# FMC.net
KiCad netlist of a schematic drawn in Altium Designer
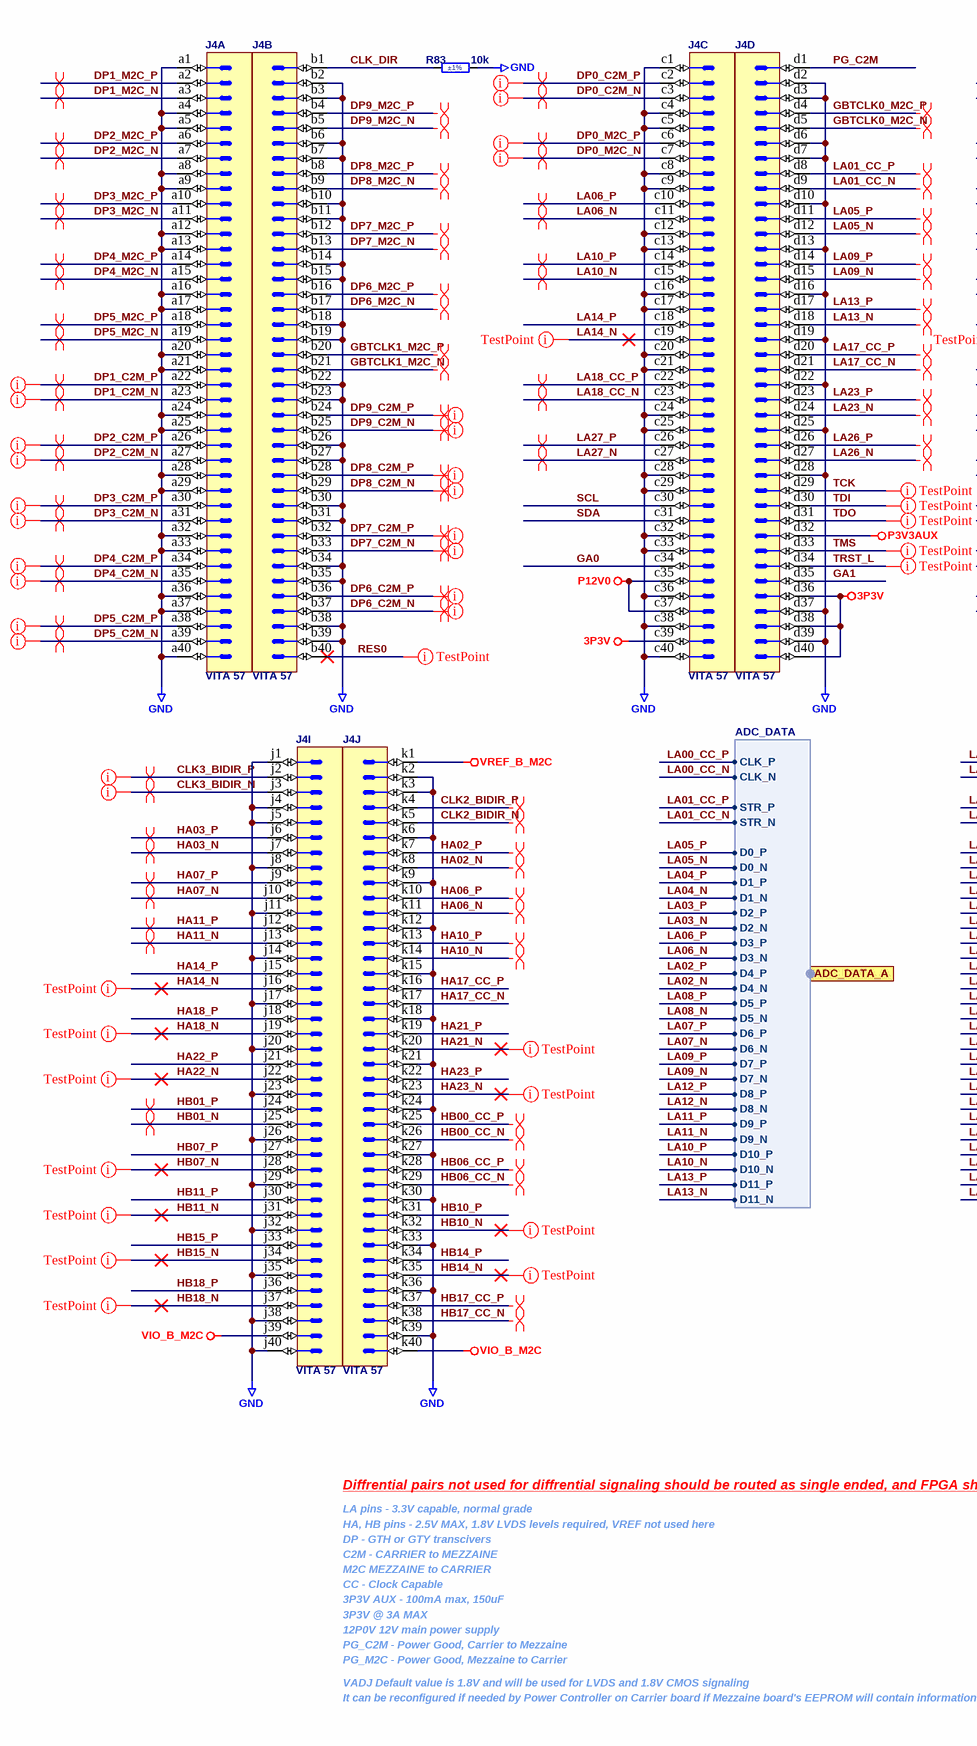
[diagram p0: FMC.SchDoc, left]
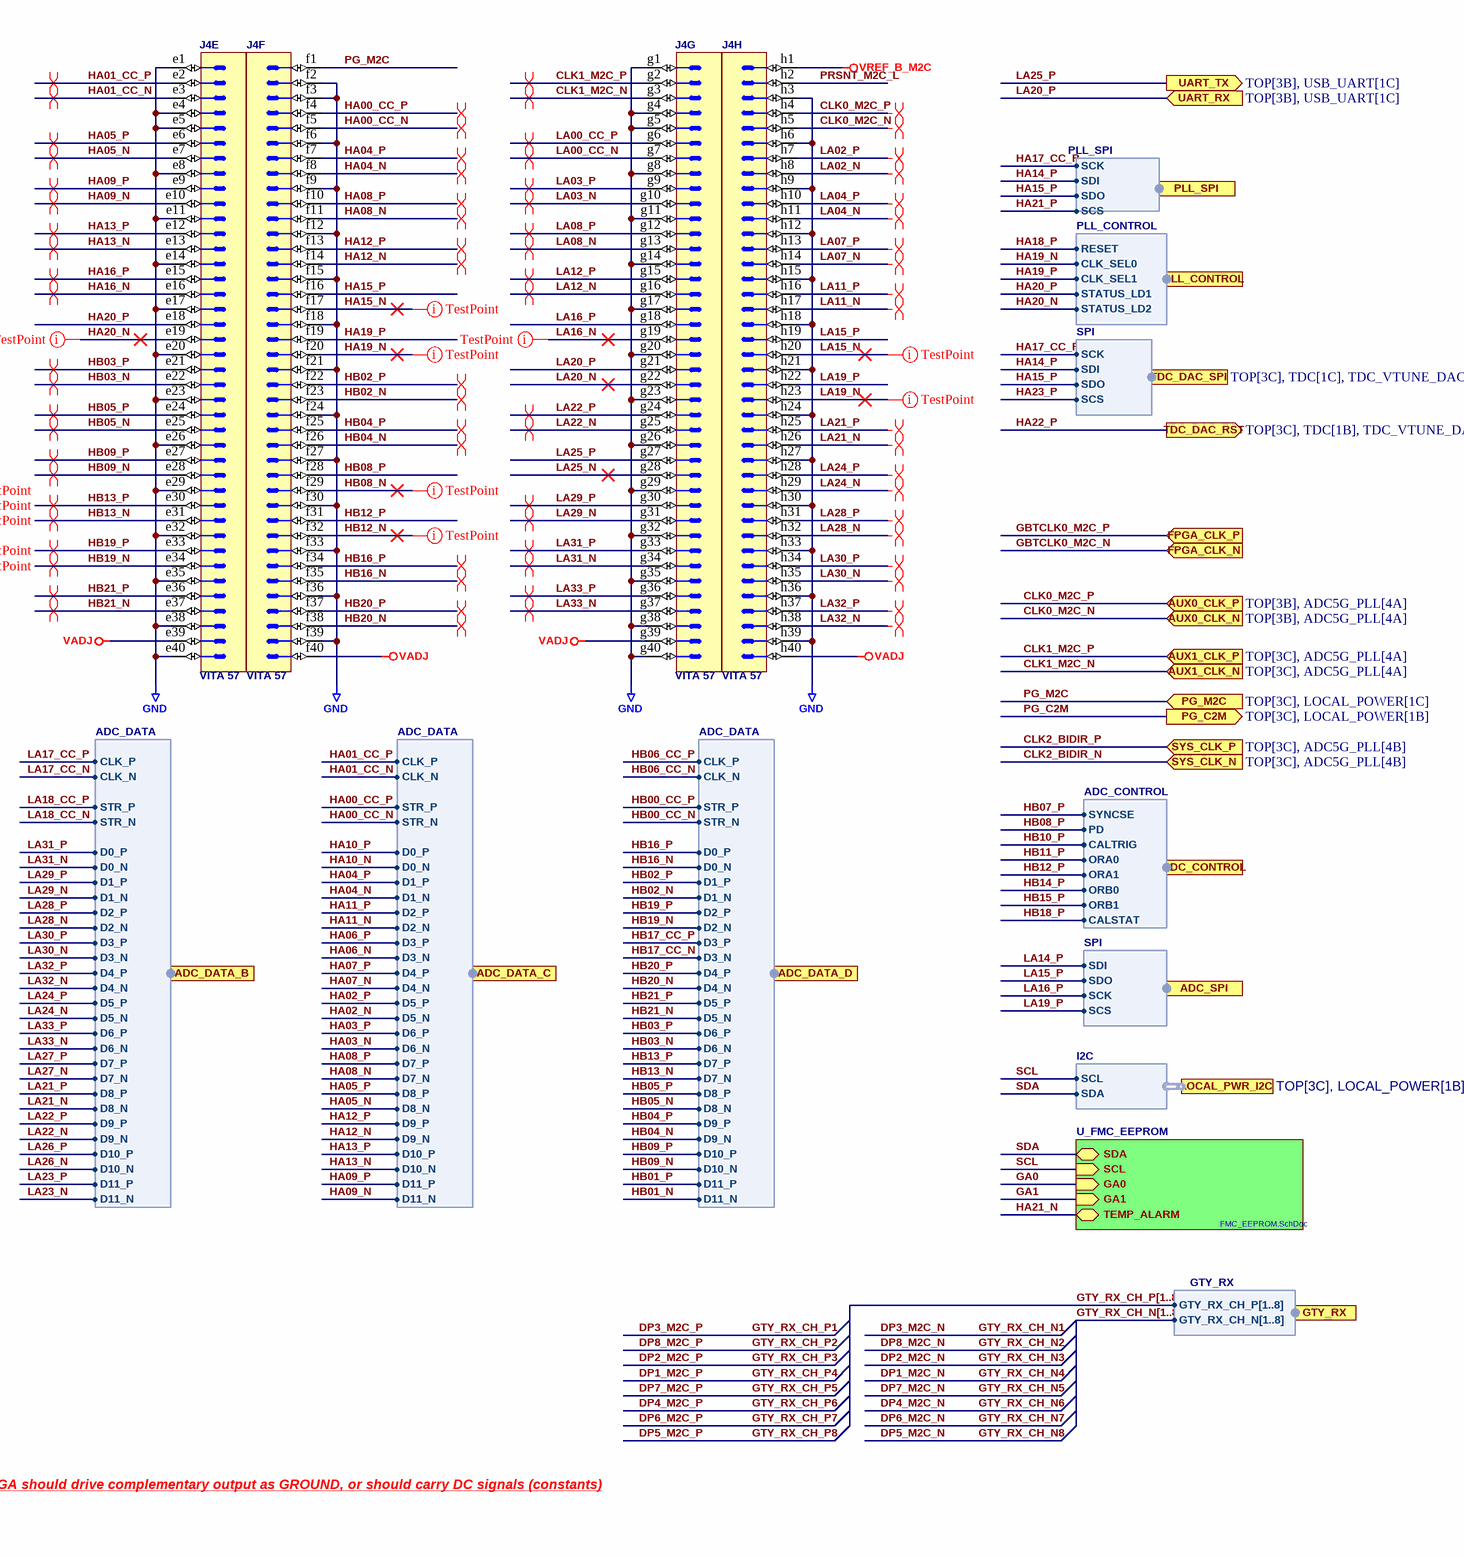
[diagram p1: FMC.SchDoc, right]

(export (version "E")
  (design (tool "Eeschema 10.0.6"))
  (components
    (comp (ref "J4")
      (value "VITA 57")
      (footprint "SAMTEC_ASP-134488-01")
      (description "Connector VITA 57, 400 Male contacts in 10 row abcdefghj")
      (fields
        (field (name "PART NUMBER") "SAMTEC_ASP-134488-01")
        (field (name "MANUFACTURER") "SAMTEC")
        (field (name "AUTHOR") "CERN DEM JLC")
      )
      (libsource (lib "Connectors") (part "Connector VITA 57 400 Male (abcdefghjk)"))
    )
    (comp (ref "R83")
      (value "10k")
      (footprint "RESC1005X40N")
      (description "Resistor - 1%")
      (fields
        (field (name "TOLERANCE") "±1%")
        (field (name "PART NUMBER") "R0402_10K_1%_0.0625W_100PPM")
        (field (name "POWER") "0.0625W")
        (field (name "AUTHOR") "CERN DEM JLC")
      )
      (libsource (lib "Resistors") (part "Resistor - 1%"))
    )
  )
  (nets
    (net (code "8") (name "/CLK0_M2C_N") (class "Default")
      (node (ref "J4") (pin "h5") (pinfunction "h5_h5") (pintype "bidirectional"))
    )
    (net (code "9") (name "/CLK0_M2C_P") (class "Default")
      (node (ref "J4") (pin "h4") (pinfunction "h4_h4") (pintype "bidirectional"))
    )
    (net (code "10") (name "/CLK1_M2C_N") (class "Default")
      (node (ref "J4") (pin "g3") (pinfunction "g3_g3") (pintype "bidirectional"))
    )
    (net (code "11") (name "/CLK1_M2C_P") (class "Default")
      (node (ref "J4") (pin "g2") (pinfunction "g2_g2") (pintype "bidirectional"))
    )
    (net (code "12") (name "/CLK2_BIDIR_N") (class "Default")
      (node (ref "J4") (pin "k5") (pinfunction "k5_k5") (pintype "bidirectional"))
    )
    (net (code "13") (name "/CLK2_BIDIR_P") (class "Default")
      (node (ref "J4") (pin "k4") (pinfunction "k4_k4") (pintype "bidirectional"))
    )
    (net (code "14") (name "/CLK3_BIDIR_N") (class "Default")
      (node (ref "J4") (pin "j3") (pinfunction "j3_j3") (pintype "bidirectional"))
    )
    (net (code "15") (name "/CLK3_BIDIR_P") (class "Default")
      (node (ref "J4") (pin "j2") (pinfunction "j2_j2") (pintype "bidirectional"))
    )
    (net (code "16") (name "/CLK_DIR") (class "Default")
      (node (ref "J4") (pin "b1") (pinfunction "b1_b1") (pintype "bidirectional"))
      (node (ref "R83") (pin "1") (pinfunction "1_1") (pintype "passive"))
    )
    (net (code "17") (name "/DP0_C2M_N") (class "Default")
      (node (ref "J4") (pin "c3") (pinfunction "c3_c3") (pintype "bidirectional"))
    )
    (net (code "18") (name "/DP0_C2M_P") (class "Default")
      (node (ref "J4") (pin "c2") (pinfunction "c2_c2") (pintype "bidirectional"))
    )
    (net (code "19") (name "/DP0_M2C_N") (class "Default")
      (node (ref "J4") (pin "c7") (pinfunction "c7_c7") (pintype "bidirectional"))
    )
    (net (code "20") (name "/DP0_M2C_P") (class "Default")
      (node (ref "J4") (pin "c6") (pinfunction "c6_c6") (pintype "bidirectional"))
    )
    (net (code "21") (name "/DP1_C2M_N") (class "Default")
      (node (ref "J4") (pin "a23") (pinfunction "a23_a23") (pintype "bidirectional"))
    )
    (net (code "22") (name "/DP1_C2M_P") (class "Default")
      (node (ref "J4") (pin "a22") (pinfunction "a22_a22") (pintype "bidirectional"))
    )
    (net (code "23") (name "/DP1_M2C_N") (class "Default")
      (node (ref "J4") (pin "a3") (pinfunction "a3_a3") (pintype "bidirectional"))
    )
    (net (code "24") (name "/DP2_C2M_N") (class "Default")
      (node (ref "J4") (pin "a27") (pinfunction "a27_a27") (pintype "bidirectional"))
    )
    (net (code "25") (name "/DP2_C2M_P") (class "Default")
      (node (ref "J4") (pin "a26") (pinfunction "a26_a26") (pintype "bidirectional"))
    )
    (net (code "26") (name "/DP2_M2C_N") (class "Default")
      (node (ref "J4") (pin "a7") (pinfunction "a7_a7") (pintype "bidirectional"))
    )
    (net (code "27") (name "/DP3_C2M_N") (class "Default")
      (node (ref "J4") (pin "a31") (pinfunction "a31_a31") (pintype "bidirectional"))
    )
    (net (code "28") (name "/DP3_C2M_P") (class "Default")
      (node (ref "J4") (pin "a30") (pinfunction "a30_a30") (pintype "bidirectional"))
    )
    (net (code "29") (name "/DP3_M2C_N") (class "Default")
      (node (ref "J4") (pin "a11") (pinfunction "a11_a11") (pintype "bidirectional"))
    )
    (net (code "30") (name "/DP4_C2M_N") (class "Default")
      (node (ref "J4") (pin "a35") (pinfunction "a35_a35") (pintype "bidirectional"))
    )
    (net (code "31") (name "/DP4_C2M_P") (class "Default")
      (node (ref "J4") (pin "a34") (pinfunction "a34_a34") (pintype "bidirectional"))
    )
    (net (code "32") (name "/DP4_M2C_N") (class "Default")
      (node (ref "J4") (pin "a15") (pinfunction "a15_a15") (pintype "bidirectional"))
    )
    (net (code "33") (name "/DP5_C2M_N") (class "Default")
      (node (ref "J4") (pin "a39") (pinfunction "a39_a39") (pintype "bidirectional"))
    )
    (net (code "34") (name "/DP5_C2M_P") (class "Default")
      (node (ref "J4") (pin "a38") (pinfunction "a38_a38") (pintype "bidirectional"))
    )
    (net (code "35") (name "/DP5_M2C_N") (class "Default")
      (node (ref "J4") (pin "a19") (pinfunction "a19_a19") (pintype "bidirectional"))
    )
    (net (code "36") (name "/DP6_C2M_N") (class "Default")
      (node (ref "J4") (pin "b37") (pinfunction "b37_b37") (pintype "bidirectional"))
    )
    (net (code "37") (name "/DP6_C2M_P") (class "Default")
      (node (ref "J4") (pin "b36") (pinfunction "b36_b36") (pintype "bidirectional"))
    )
    (net (code "38") (name "/DP6_M2C_N") (class "Default")
      (node (ref "J4") (pin "b17") (pinfunction "b17_b17") (pintype "bidirectional"))
    )
    (net (code "39") (name "/DP7_C2M_N") (class "Default")
      (node (ref "J4") (pin "b33") (pinfunction "b33_b33") (pintype "bidirectional"))
    )
    (net (code "40") (name "/DP7_C2M_P") (class "Default")
      (node (ref "J4") (pin "b32") (pinfunction "b32_b32") (pintype "bidirectional"))
    )
    (net (code "41") (name "/DP7_M2C_N") (class "Default")
      (node (ref "J4") (pin "b13") (pinfunction "b13_b13") (pintype "bidirectional"))
    )
    (net (code "42") (name "/DP8_C2M_N") (class "Default")
      (node (ref "J4") (pin "b29") (pinfunction "b29_b29") (pintype "bidirectional"))
    )
    (net (code "43") (name "/DP8_C2M_P") (class "Default")
      (node (ref "J4") (pin "b28") (pinfunction "b28_b28") (pintype "bidirectional"))
    )
    (net (code "44") (name "/DP8_M2C_N") (class "Default")
      (node (ref "J4") (pin "b9") (pinfunction "b9_b9") (pintype "bidirectional"))
    )
    (net (code "45") (name "/DP9_C2M_N") (class "Default")
      (node (ref "J4") (pin "b25") (pinfunction "b25_b25") (pintype "bidirectional"))
    )
    (net (code "46") (name "/DP9_C2M_P") (class "Default")
      (node (ref "J4") (pin "b24") (pinfunction "b24_b24") (pintype "bidirectional"))
    )
    (net (code "47") (name "/DP9_M2C_N") (class "Default")
      (node (ref "J4") (pin "b5") (pinfunction "b5_b5") (pintype "bidirectional"))
    )
    (net (code "48") (name "/DP9_M2C_P") (class "Default")
      (node (ref "J4") (pin "b4") (pinfunction "b4_b4") (pintype "bidirectional"))
    )
    (net (code "49") (name "/GA0") (class "Default")
      (node (ref "J4") (pin "c34") (pinfunction "c34_c34") (pintype "bidirectional"))
    )
    (net (code "50") (name "/GA1") (class "Default")
      (node (ref "J4") (pin "d35") (pinfunction "d35_d35") (pintype "bidirectional"))
    )
    (net (code "51") (name "/GBTCLK0_M2C_N") (class "Default")
      (node (ref "J4") (pin "d5") (pinfunction "d5_d5") (pintype "bidirectional"))
    )
    (net (code "52") (name "/GBTCLK0_M2C_P") (class "Default")
      (node (ref "J4") (pin "d4") (pinfunction "d4_d4") (pintype "bidirectional"))
    )
    (net (code "53") (name "/GBTCLK1_M2C_N") (class "Default")
      (node (ref "J4") (pin "b21") (pinfunction "b21_b21") (pintype "bidirectional"))
    )
    (net (code "54") (name "/GBTCLK1_M2C_P") (class "Default")
      (node (ref "J4") (pin "b20") (pinfunction "b20_b20") (pintype "bidirectional"))
    )
    (net (code "55") (name "/GTY_RX_CH_P1") (class "Default")
      (node (ref "J4") (pin "a10") (pinfunction "a10_a10") (pintype "bidirectional"))
    )
    (net (code "56") (name "/GTY_RX_CH_P2") (class "Default")
      (node (ref "J4") (pin "b8") (pinfunction "b8_b8") (pintype "bidirectional"))
    )
    (net (code "57") (name "/GTY_RX_CH_P3") (class "Default")
      (node (ref "J4") (pin "a6") (pinfunction "a6_a6") (pintype "bidirectional"))
    )
    (net (code "58") (name "/GTY_RX_CH_P4") (class "Default")
      (node (ref "J4") (pin "a2") (pinfunction "a2_a2") (pintype "bidirectional"))
    )
    (net (code "59") (name "/GTY_RX_CH_P5") (class "Default")
      (node (ref "J4") (pin "b12") (pinfunction "b12_b12") (pintype "bidirectional"))
    )
    (net (code "60") (name "/GTY_RX_CH_P6") (class "Default")
      (node (ref "J4") (pin "a14") (pinfunction "a14_a14") (pintype "bidirectional"))
    )
    (net (code "61") (name "/GTY_RX_CH_P7") (class "Default")
      (node (ref "J4") (pin "b16") (pinfunction "b16_b16") (pintype "bidirectional"))
    )
    (net (code "62") (name "/GTY_RX_CH_P8") (class "Default")
      (node (ref "J4") (pin "a18") (pinfunction "a18_a18") (pintype "bidirectional"))
    )
    (net (code "65") (name "/HA00_CC_N") (class "Default")
      (node (ref "J4") (pin "f5") (pinfunction "f5_f5") (pintype "bidirectional"))
    )
    (net (code "66") (name "/HA00_CC_P") (class "Default")
      (node (ref "J4") (pin "f4") (pinfunction "f4_f4") (pintype "bidirectional"))
    )
    (net (code "67") (name "/HA01_CC_N") (class "Default")
      (node (ref "J4") (pin "e3") (pinfunction "e3_e3") (pintype "bidirectional"))
    )
    (net (code "68") (name "/HA01_CC_P") (class "Default")
      (node (ref "J4") (pin "e2") (pinfunction "e2_e2") (pintype "bidirectional"))
    )
    (net (code "69") (name "/HA02_N") (class "Default")
      (node (ref "J4") (pin "k8") (pinfunction "k8_k8") (pintype "bidirectional"))
    )
    (net (code "70") (name "/HA02_P") (class "Default")
      (node (ref "J4") (pin "k7") (pinfunction "k7_k7") (pintype "bidirectional"))
    )
    (net (code "71") (name "/HA03_N") (class "Default")
      (node (ref "J4") (pin "j7") (pinfunction "j7_j7") (pintype "bidirectional"))
    )
    (net (code "72") (name "/HA03_P") (class "Default")
      (node (ref "J4") (pin "j6") (pinfunction "j6_j6") (pintype "bidirectional"))
    )
    (net (code "73") (name "/HA04_N") (class "Default")
      (node (ref "J4") (pin "f8") (pinfunction "f8_f8") (pintype "bidirectional"))
    )
    (net (code "74") (name "/HA04_P") (class "Default")
      (node (ref "J4") (pin "f7") (pinfunction "f7_f7") (pintype "bidirectional"))
    )
    (net (code "75") (name "/HA05_N") (class "Default")
      (node (ref "J4") (pin "e7") (pinfunction "e7_e7") (pintype "bidirectional"))
    )
    (net (code "76") (name "/HA05_P") (class "Default")
      (node (ref "J4") (pin "e6") (pinfunction "e6_e6") (pintype "bidirectional"))
    )
    (net (code "77") (name "/HA06_N") (class "Default")
      (node (ref "J4") (pin "k11") (pinfunction "k11_k11") (pintype "bidirectional"))
    )
    (net (code "78") (name "/HA06_P") (class "Default")
      (node (ref "J4") (pin "k10") (pinfunction "k10_k10") (pintype "bidirectional"))
    )
    (net (code "79") (name "/HA07_N") (class "Default")
      (node (ref "J4") (pin "j10") (pinfunction "j10_j10") (pintype "bidirectional"))
    )
    (net (code "80") (name "/HA07_P") (class "Default")
      (node (ref "J4") (pin "j9") (pinfunction "j9_j9") (pintype "bidirectional"))
    )
    (net (code "81") (name "/HA08_N") (class "Default")
      (node (ref "J4") (pin "f11") (pinfunction "f11_f11") (pintype "bidirectional"))
    )
    (net (code "82") (name "/HA08_P") (class "Default")
      (node (ref "J4") (pin "f10") (pinfunction "f10_f10") (pintype "bidirectional"))
    )
    (net (code "83") (name "/HA09_N") (class "Default")
      (node (ref "J4") (pin "e10") (pinfunction "e10_e10") (pintype "bidirectional"))
    )
    (net (code "84") (name "/HA09_P") (class "Default")
      (node (ref "J4") (pin "e9") (pinfunction "e9_e9") (pintype "bidirectional"))
    )
    (net (code "85") (name "/HA10_N") (class "Default")
      (node (ref "J4") (pin "k14") (pinfunction "k14_k14") (pintype "bidirectional"))
    )
    (net (code "86") (name "/HA10_P") (class "Default")
      (node (ref "J4") (pin "k13") (pinfunction "k13_k13") (pintype "bidirectional"))
    )
    (net (code "87") (name "/HA11_N") (class "Default")
      (node (ref "J4") (pin "j13") (pinfunction "j13_j13") (pintype "bidirectional"))
    )
    (net (code "88") (name "/HA11_P") (class "Default")
      (node (ref "J4") (pin "j12") (pinfunction "j12_j12") (pintype "bidirectional"))
    )
    (net (code "89") (name "/HA12_N") (class "Default")
      (node (ref "J4") (pin "f14") (pinfunction "f14_f14") (pintype "bidirectional"))
    )
    (net (code "90") (name "/HA12_P") (class "Default")
      (node (ref "J4") (pin "f13") (pinfunction "f13_f13") (pintype "bidirectional"))
    )
    (net (code "91") (name "/HA13_N") (class "Default")
      (node (ref "J4") (pin "e13") (pinfunction "e13_e13") (pintype "bidirectional"))
    )
    (net (code "92") (name "/HA13_P") (class "Default")
      (node (ref "J4") (pin "e12") (pinfunction "e12_e12") (pintype "bidirectional"))
    )
    (net (code "93") (name "/HA14_N") (class "Default")
      (node (ref "J4") (pin "j16") (pinfunction "j16_j16") (pintype "bidirectional"))
    )
    (net (code "94") (name "/HA14_P") (class "Default")
      (node (ref "J4") (pin "j15") (pinfunction "j15_j15") (pintype "bidirectional"))
    )
    (net (code "95") (name "/HA15_N") (class "Default")
      (node (ref "J4") (pin "f17") (pinfunction "f17_f17") (pintype "bidirectional"))
    )
    (net (code "96") (name "/HA15_P") (class "Default")
      (node (ref "J4") (pin "f16") (pinfunction "f16_f16") (pintype "bidirectional"))
    )
    (net (code "97") (name "/HA16_N") (class "Default")
      (node (ref "J4") (pin "e16") (pinfunction "e16_e16") (pintype "bidirectional"))
    )
    (net (code "98") (name "/HA16_P") (class "Default")
      (node (ref "J4") (pin "e15") (pinfunction "e15_e15") (pintype "bidirectional"))
    )
    (net (code "99") (name "/HA17_CC_N") (class "Default")
      (node (ref "J4") (pin "k17") (pinfunction "k17_k17") (pintype "bidirectional"))
    )
    (net (code "100") (name "/HA17_CC_P") (class "Default")
      (node (ref "J4") (pin "k16") (pinfunction "k16_k16") (pintype "bidirectional"))
    )
    (net (code "101") (name "/HA18_N") (class "Default")
      (node (ref "J4") (pin "j19") (pinfunction "j19_j19") (pintype "bidirectional"))
    )
    (net (code "102") (name "/HA18_P") (class "Default")
      (node (ref "J4") (pin "j18") (pinfunction "j18_j18") (pintype "bidirectional"))
    )
    (net (code "103") (name "/HA19_N") (class "Default")
      (node (ref "J4") (pin "f20") (pinfunction "f20_f20") (pintype "bidirectional"))
    )
    (net (code "104") (name "/HA19_P") (class "Default")
      (node (ref "J4") (pin "f19") (pinfunction "f19_f19") (pintype "bidirectional"))
    )
    (net (code "105") (name "/HA20_N") (class "Default")
      (node (ref "J4") (pin "e19") (pinfunction "e19_e19") (pintype "bidirectional"))
    )
    (net (code "106") (name "/HA20_P") (class "Default")
      (node (ref "J4") (pin "e18") (pinfunction "e18_e18") (pintype "bidirectional"))
    )
    (net (code "107") (name "/HA21_N") (class "Default")
      (node (ref "J4") (pin "k20") (pinfunction "k20_k20") (pintype "bidirectional"))
    )
    (net (code "108") (name "/HA21_P") (class "Default")
      (node (ref "J4") (pin "k19") (pinfunction "k19_k19") (pintype "bidirectional"))
    )
    (net (code "109") (name "/HA22_N") (class "Default")
      (node (ref "J4") (pin "j22") (pinfunction "j22_j22") (pintype "bidirectional"))
    )
    (net (code "110") (name "/HA22_P") (class "Default")
      (node (ref "J4") (pin "j21") (pinfunction "j21_j21") (pintype "bidirectional"))
    )
    (net (code "111") (name "/HA23_N") (class "Default")
      (node (ref "J4") (pin "k23") (pinfunction "k23_k23") (pintype "bidirectional"))
    )
    (net (code "112") (name "/HA23_P") (class "Default")
      (node (ref "J4") (pin "k22") (pinfunction "k22_k22") (pintype "bidirectional"))
    )
    (net (code "113") (name "/HB00_CC_N") (class "Default")
      (node (ref "J4") (pin "k26") (pinfunction "k26_k26") (pintype "bidirectional"))
    )
    (net (code "114") (name "/HB00_CC_P") (class "Default")
      (node (ref "J4") (pin "k25") (pinfunction "k25_k25") (pintype "bidirectional"))
    )
    (net (code "115") (name "/HB01_N") (class "Default")
      (node (ref "J4") (pin "j25") (pinfunction "j25_j25") (pintype "bidirectional"))
    )
    (net (code "116") (name "/HB01_P") (class "Default")
      (node (ref "J4") (pin "j24") (pinfunction "j24_j24") (pintype "bidirectional"))
    )
    (net (code "117") (name "/HB02_N") (class "Default")
      (node (ref "J4") (pin "f23") (pinfunction "f23_f23") (pintype "bidirectional"))
    )
    (net (code "118") (name "/HB02_P") (class "Default")
      (node (ref "J4") (pin "f22") (pinfunction "f22_f22") (pintype "bidirectional"))
    )
    (net (code "119") (name "/HB03_N") (class "Default")
      (node (ref "J4") (pin "e22") (pinfunction "e22_e22") (pintype "bidirectional"))
    )
    (net (code "120") (name "/HB03_P") (class "Default")
      (node (ref "J4") (pin "e21") (pinfunction "e21_e21") (pintype "bidirectional"))
    )
    (net (code "121") (name "/HB04_N") (class "Default")
      (node (ref "J4") (pin "f26") (pinfunction "f26_f26") (pintype "bidirectional"))
    )
    (net (code "122") (name "/HB04_P") (class "Default")
      (node (ref "J4") (pin "f25") (pinfunction "f25_f25") (pintype "bidirectional"))
    )
    (net (code "123") (name "/HB05_N") (class "Default")
      (node (ref "J4") (pin "e25") (pinfunction "e25_e25") (pintype "bidirectional"))
    )
    (net (code "124") (name "/HB05_P") (class "Default")
      (node (ref "J4") (pin "e24") (pinfunction "e24_e24") (pintype "bidirectional"))
    )
    (net (code "125") (name "/HB06_CC_N") (class "Default")
      (node (ref "J4") (pin "k29") (pinfunction "k29_k29") (pintype "bidirectional"))
    )
    (net (code "126") (name "/HB06_CC_P") (class "Default")
      (node (ref "J4") (pin "k28") (pinfunction "k28_k28") (pintype "bidirectional"))
    )
    (net (code "127") (name "/HB07_N") (class "Default")
      (node (ref "J4") (pin "j28") (pinfunction "j28_j28") (pintype "bidirectional"))
    )
    (net (code "128") (name "/HB07_P") (class "Default")
      (node (ref "J4") (pin "j27") (pinfunction "j27_j27") (pintype "bidirectional"))
    )
    (net (code "129") (name "/HB08_N") (class "Default")
      (node (ref "J4") (pin "f29") (pinfunction "f29_f29") (pintype "bidirectional"))
    )
    (net (code "130") (name "/HB08_P") (class "Default")
      (node (ref "J4") (pin "f28") (pinfunction "f28_f28") (pintype "bidirectional"))
    )
    (net (code "131") (name "/HB09_N") (class "Default")
      (node (ref "J4") (pin "e28") (pinfunction "e28_e28") (pintype "bidirectional"))
    )
    (net (code "132") (name "/HB09_P") (class "Default")
      (node (ref "J4") (pin "e27") (pinfunction "e27_e27") (pintype "bidirectional"))
    )
    (net (code "133") (name "/HB10_N") (class "Default")
      (node (ref "J4") (pin "k32") (pinfunction "k32_k32") (pintype "bidirectional"))
    )
    (net (code "134") (name "/HB10_P") (class "Default")
      (node (ref "J4") (pin "k31") (pinfunction "k31_k31") (pintype "bidirectional"))
    )
    (net (code "135") (name "/HB11_N") (class "Default")
      (node (ref "J4") (pin "j31") (pinfunction "j31_j31") (pintype "bidirectional"))
    )
    (net (code "136") (name "/HB11_P") (class "Default")
      (node (ref "J4") (pin "j30") (pinfunction "j30_j30") (pintype "bidirectional"))
    )
    (net (code "137") (name "/HB12_N") (class "Default")
      (node (ref "J4") (pin "f32") (pinfunction "f32_f32") (pintype "bidirectional"))
    )
    (net (code "138") (name "/HB12_P") (class "Default")
      (node (ref "J4") (pin "f31") (pinfunction "f31_f31") (pintype "bidirectional"))
    )
    (net (code "139") (name "/HB13_N") (class "Default")
      (node (ref "J4") (pin "e31") (pinfunction "e31_e31") (pintype "bidirectional"))
    )
    (net (code "140") (name "/HB13_P") (class "Default")
      (node (ref "J4") (pin "e30") (pinfunction "e30_e30") (pintype "bidirectional"))
    )
    (net (code "141") (name "/HB14_N") (class "Default")
      (node (ref "J4") (pin "k35") (pinfunction "k35_k35") (pintype "bidirectional"))
    )
    (net (code "142") (name "/HB14_P") (class "Default")
      (node (ref "J4") (pin "k34") (pinfunction "k34_k34") (pintype "bidirectional"))
    )
    (net (code "143") (name "/HB15_N") (class "Default")
      (node (ref "J4") (pin "j34") (pinfunction "j34_j34") (pintype "bidirectional"))
    )
    (net (code "144") (name "/HB15_P") (class "Default")
      (node (ref "J4") (pin "j33") (pinfunction "j33_j33") (pintype "bidirectional"))
    )
    (net (code "145") (name "/HB16_N") (class "Default")
      (node (ref "J4") (pin "f35") (pinfunction "f35_f35") (pintype "bidirectional"))
    )
    (net (code "146") (name "/HB16_P") (class "Default")
      (node (ref "J4") (pin "f34") (pinfunction "f34_f34") (pintype "bidirectional"))
    )
    (net (code "147") (name "/HB17_CC_N") (class "Default")
      (node (ref "J4") (pin "k38") (pinfunction "k38_k38") (pintype "bidirectional"))
    )
    (net (code "148") (name "/HB17_CC_P") (class "Default")
      (node (ref "J4") (pin "k37") (pinfunction "k37_k37") (pintype "bidirectional"))
    )
    (net (code "149") (name "/HB18_N") (class "Default")
      (node (ref "J4") (pin "j37") (pinfunction "j37_j37") (pintype "bidirectional"))
    )
    (net (code "150") (name "/HB18_P") (class "Default")
      (node (ref "J4") (pin "j36") (pinfunction "j36_j36") (pintype "bidirectional"))
    )
    (net (code "151") (name "/HB19_N") (class "Default")
      (node (ref "J4") (pin "e34") (pinfunction "e34_e34") (pintype "bidirectional"))
    )
    (net (code "152") (name "/HB19_P") (class "Default")
      (node (ref "J4") (pin "e33") (pinfunction "e33_e33") (pintype "bidirectional"))
    )
    (net (code "153") (name "/HB20_N") (class "Default")
      (node (ref "J4") (pin "f38") (pinfunction "f38_f38") (pintype "bidirectional"))
    )
    (net (code "154") (name "/HB20_P") (class "Default")
      (node (ref "J4") (pin "f37") (pinfunction "f37_f37") (pintype "bidirectional"))
    )
    (net (code "155") (name "/HB21_N") (class "Default")
      (node (ref "J4") (pin "e37") (pinfunction "e37_e37") (pintype "bidirectional"))
    )
    (net (code "156") (name "/HB21_P") (class "Default")
      (node (ref "J4") (pin "e36") (pinfunction "e36_e36") (pintype "bidirectional"))
    )
    (net (code "157") (name "/LA00_CC_N") (class "Default")
      (node (ref "J4") (pin "g7") (pinfunction "g7_g7") (pintype "bidirectional"))
    )
    (net (code "158") (name "/LA00_CC_P") (class "Default")
      (node (ref "J4") (pin "g6") (pinfunction "g6_g6") (pintype "bidirectional"))
    )
    (net (code "159") (name "/LA01_CC_N") (class "Default")
      (node (ref "J4") (pin "d9") (pinfunction "d9_d9") (pintype "bidirectional"))
    )
    (net (code "160") (name "/LA01_CC_P") (class "Default")
      (node (ref "J4") (pin "d8") (pinfunction "d8_d8") (pintype "bidirectional"))
    )
    (net (code "161") (name "/LA02_N") (class "Default")
      (node (ref "J4") (pin "h8") (pinfunction "h8_h8") (pintype "bidirectional"))
    )
    (net (code "162") (name "/LA02_P") (class "Default")
      (node (ref "J4") (pin "h7") (pinfunction "h7_h7") (pintype "bidirectional"))
    )
    (net (code "163") (name "/LA03_N") (class "Default")
      (node (ref "J4") (pin "g10") (pinfunction "g10_g10") (pintype "bidirectional"))
    )
    (net (code "164") (name "/LA03_P") (class "Default")
      (node (ref "J4") (pin "g9") (pinfunction "g9_g9") (pintype "bidirectional"))
    )
    (net (code "165") (name "/LA04_N") (class "Default")
      (node (ref "J4") (pin "h11") (pinfunction "h11_h11") (pintype "bidirectional"))
    )
    (net (code "166") (name "/LA04_P") (class "Default")
      (node (ref "J4") (pin "h10") (pinfunction "h10_h10") (pintype "bidirectional"))
    )
    (net (code "167") (name "/LA05_N") (class "Default")
      (node (ref "J4") (pin "d12") (pinfunction "d12_d12") (pintype "bidirectional"))
    )
    (net (code "168") (name "/LA05_P") (class "Default")
      (node (ref "J4") (pin "d11") (pinfunction "d11_d11") (pintype "bidirectional"))
    )
    (net (code "169") (name "/LA06_N") (class "Default")
      (node (ref "J4") (pin "c11") (pinfunction "c11_c11") (pintype "bidirectional"))
    )
    (net (code "170") (name "/LA06_P") (class "Default")
      (node (ref "J4") (pin "c10") (pinfunction "c10_c10") (pintype "bidirectional"))
    )
    (net (code "171") (name "/LA07_N") (class "Default")
      (node (ref "J4") (pin "h14") (pinfunction "h14_h14") (pintype "bidirectional"))
    )
    (net (code "172") (name "/LA07_P") (class "Default")
      (node (ref "J4") (pin "h13") (pinfunction "h13_h13") (pintype "bidirectional"))
    )
    (net (code "173") (name "/LA08_N") (class "Default")
      (node (ref "J4") (pin "g13") (pinfunction "g13_g13") (pintype "bidirectional"))
    )
    (net (code "174") (name "/LA08_P") (class "Default")
      (node (ref "J4") (pin "g12") (pinfunction "g12_g12") (pintype "bidirectional"))
    )
    (net (code "175") (name "/LA09_N") (class "Default")
      (node (ref "J4") (pin "d15") (pinfunction "d15_d15") (pintype "bidirectional"))
    )
    (net (code "176") (name "/LA09_P") (class "Default")
      (node (ref "J4") (pin "d14") (pinfunction "d14_d14") (pintype "bidirectional"))
    )
    (net (code "177") (name "/LA10_N") (class "Default")
      (node (ref "J4") (pin "c15") (pinfunction "c15_c15") (pintype "bidirectional"))
    )
    (net (code "178") (name "/LA10_P") (class "Default")
      (node (ref "J4") (pin "c14") (pinfunction "c14_c14") (pintype "bidirectional"))
    )
    (net (code "179") (name "/LA11_N") (class "Default")
      (node (ref "J4") (pin "h17") (pinfunction "h17_h17") (pintype "bidirectional"))
    )
    (net (code "180") (name "/LA11_P") (class "Default")
      (node (ref "J4") (pin "h16") (pinfunction "h16_h16") (pintype "bidirectional"))
    )
    (net (code "181") (name "/LA12_N") (class "Default")
      (node (ref "J4") (pin "g16") (pinfunction "g16_g16") (pintype "bidirectional"))
    )
    (net (code "182") (name "/LA12_P") (class "Default")
      (node (ref "J4") (pin "g15") (pinfunction "g15_g15") (pintype "bidirectional"))
    )
    (net (code "183") (name "/LA13_N") (class "Default")
      (node (ref "J4") (pin "d18") (pinfunction "d18_d18") (pintype "bidirectional"))
    )
    (net (code "184") (name "/LA13_P") (class "Default")
      (node (ref "J4") (pin "d17") (pinfunction "d17_d17") (pintype "bidirectional"))
    )
    (net (code "185") (name "/LA14_N") (class "Default")
      (node (ref "J4") (pin "c19") (pinfunction "c19_c19") (pintype "bidirectional"))
    )
    (net (code "186") (name "/LA14_P") (class "Default")
      (node (ref "J4") (pin "c18") (pinfunction "c18_c18") (pintype "bidirectional"))
    )
    (net (code "187") (name "/LA15_N") (class "Default")
      (node (ref "J4") (pin "h20") (pinfunction "h20_h20") (pintype "bidirectional"))
    )
    (net (code "188") (name "/LA15_P") (class "Default")
      (node (ref "J4") (pin "h19") (pinfunction "h19_h19") (pintype "bidirectional"))
    )
    (net (code "189") (name "/LA16_N") (class "Default")
      (node (ref "J4") (pin "g19") (pinfunction "g19_g19") (pintype "bidirectional"))
    )
    (net (code "190") (name "/LA16_P") (class "Default")
      (node (ref "J4") (pin "g18") (pinfunction "g18_g18") (pintype "bidirectional"))
    )
    (net (code "191") (name "/LA17_CC_N") (class "Default")
      (node (ref "J4") (pin "d21") (pinfunction "d21_d21") (pintype "bidirectional"))
    )
    (net (code "192") (name "/LA17_CC_P") (class "Default")
      (node (ref "J4") (pin "d20") (pinfunction "d20_d20") (pintype "bidirectional"))
    )
    (net (code "193") (name "/LA18_CC_N") (class "Default")
      (node (ref "J4") (pin "c23") (pinfunction "c23_c23") (pintype "bidirectional"))
    )
    (net (code "194") (name "/LA18_CC_P") (class "Default")
      (node (ref "J4") (pin "c22") (pinfunction "c22_c22") (pintype "bidirectional"))
    )
    (net (code "195") (name "/LA19_N") (class "Default")
      (node (ref "J4") (pin "h23") (pinfunction "h23_h23") (pintype "bidirectional"))
    )
    (net (code "196") (name "/LA19_P") (class "Default")
      (node (ref "J4") (pin "h22") (pinfunction "h22_h22") (pintype "bidirectional"))
    )
    (net (code "197") (name "/LA20_N") (class "Default")
      (node (ref "J4") (pin "g22") (pinfunction "g22_g22") (pintype "bidirectional"))
    )
    (net (code "198") (name "/LA20_P") (class "Default")
      (node (ref "J4") (pin "g21") (pinfunction "g21_g21") (pintype "bidirectional"))
    )
    (net (code "199") (name "/LA21_N") (class "Default")
      (node (ref "J4") (pin "h26") (pinfunction "h26_h26") (pintype "bidirectional"))
    )
    (net (code "200") (name "/LA21_P") (class "Default")
      (node (ref "J4") (pin "h25") (pinfunction "h25_h25") (pintype "bidirectional"))
    )
    (net (code "201") (name "/LA22_N") (class "Default")
      (node (ref "J4") (pin "g25") (pinfunction "g25_g25") (pintype "bidirectional"))
    )
    (net (code "202") (name "/LA22_P") (class "Default")
      (node (ref "J4") (pin "g24") (pinfunction "g24_g24") (pintype "bidirectional"))
    )
    (net (code "203") (name "/LA23_N") (class "Default")
      (node (ref "J4") (pin "d24") (pinfunction "d24_d24") (pintype "bidirectional"))
    )
    (net (code "204") (name "/LA23_P") (class "Default")
      (node (ref "J4") (pin "d23") (pinfunction "d23_d23") (pintype "bidirectional"))
    )
    (net (code "205") (name "/LA24_N") (class "Default")
      (node (ref "J4") (pin "h29") (pinfunction "h29_h29") (pintype "bidirectional"))
    )
    (net (code "206") (name "/LA24_P") (class "Default")
      (node (ref "J4") (pin "h28") (pinfunction "h28_h28") (pintype "bidirectional"))
    )
    (net (code "207") (name "/LA25_N") (class "Default")
      (node (ref "J4") (pin "g28") (pinfunction "g28_g28") (pintype "bidirectional"))
    )
    (net (code "208") (name "/LA25_P") (class "Default")
      (node (ref "J4") (pin "g27") (pinfunction "g27_g27") (pintype "bidirectional"))
    )
    (net (code "209") (name "/LA26_N") (class "Default")
      (node (ref "J4") (pin "d27") (pinfunction "d27_d27") (pintype "bidirectional"))
    )
    (net (code "210") (name "/LA26_P") (class "Default")
      (node (ref "J4") (pin "d26") (pinfunction "d26_d26") (pintype "bidirectional"))
    )
    (net (code "211") (name "/LA27_N") (class "Default")
      (node (ref "J4") (pin "c27") (pinfunction "c27_c27") (pintype "bidirectional"))
    )
    (net (code "212") (name "/LA27_P") (class "Default")
      (node (ref "J4") (pin "c26") (pinfunction "c26_c26") (pintype "bidirectional"))
    )
    (net (code "213") (name "/LA28_N") (class "Default")
      (node (ref "J4") (pin "h32") (pinfunction "h32_h32") (pintype "bidirectional"))
    )
    (net (code "214") (name "/LA28_P") (class "Default")
      (node (ref "J4") (pin "h31") (pinfunction "h31_h31") (pintype "bidirectional"))
    )
    (net (code "215") (name "/LA29_N") (class "Default")
      (node (ref "J4") (pin "g31") (pinfunction "g31_g31") (pintype "bidirectional"))
    )
    (net (code "216") (name "/LA29_P") (class "Default")
      (node (ref "J4") (pin "g30") (pinfunction "g30_g30") (pintype "bidirectional"))
    )
    (net (code "217") (name "/LA30_N") (class "Default")
      (node (ref "J4") (pin "h35") (pinfunction "h35_h35") (pintype "bidirectional"))
    )
    (net (code "218") (name "/LA30_P") (class "Default")
      (node (ref "J4") (pin "h34") (pinfunction "h34_h34") (pintype "bidirectional"))
    )
    (net (code "219") (name "/LA31_N") (class "Default")
      (node (ref "J4") (pin "g34") (pinfunction "g34_g34") (pintype "bidirectional"))
    )
    (net (code "220") (name "/LA31_P") (class "Default")
      (node (ref "J4") (pin "g33") (pinfunction "g33_g33") (pintype "bidirectional"))
    )
    (net (code "221") (name "/LA32_N") (class "Default")
      (node (ref "J4") (pin "h38") (pinfunction "h38_h38") (pintype "bidirectional"))
    )
    (net (code "222") (name "/LA32_P") (class "Default")
      (node (ref "J4") (pin "h37") (pinfunction "h37_h37") (pintype "bidirectional"))
    )
    (net (code "223") (name "/LA33_N") (class "Default")
      (node (ref "J4") (pin "g37") (pinfunction "g37_g37") (pintype "bidirectional"))
    )
    (net (code "224") (name "/LA33_P") (class "Default")
      (node (ref "J4") (pin "g36") (pinfunction "g36_g36") (pintype "bidirectional"))
    )
    (net (code "225") (name "/PG_C2M") (class "Default")
      (node (ref "J4") (pin "d1") (pinfunction "d1_d1") (pintype "bidirectional"))
    )
    (net (code "226") (name "/PG_M2C") (class "Default")
      (node (ref "J4") (pin "f1") (pinfunction "f1_f1") (pintype "bidirectional"))
    )
    (net (code "227") (name "/PRSNT_M2C_L") (class "Default")
      (node (ref "J4") (pin "h2") (pinfunction "h2_h2") (pintype "bidirectional"))
    )
    (net (code "228") (name "/RES0") (class "Default")
      (node (ref "J4") (pin "b40") (pinfunction "b40_b40") (pintype "bidirectional+no_connect"))
    )
    (net (code "229") (name "/SCL") (class "Default")
      (node (ref "J4") (pin "c30") (pinfunction "c30_c30") (pintype "bidirectional"))
    )
    (net (code "230") (name "/SDA") (class "Default")
      (node (ref "J4") (pin "c31") (pinfunction "c31_c31") (pintype "bidirectional"))
    )
    (net (code "231") (name "/TCK") (class "Default")
      (node (ref "J4") (pin "d29") (pinfunction "d29_d29") (pintype "bidirectional"))
    )
    (net (code "232") (name "/TDI") (class "Default")
      (node (ref "J4") (pin "d30") (pinfunction "d30_d30") (pintype "bidirectional"))
    )
    (net (code "233") (name "/TDO") (class "Default")
      (node (ref "J4") (pin "d31") (pinfunction "d31_d31") (pintype "bidirectional"))
    )
    (net (code "234") (name "/TMS") (class "Default")
      (node (ref "J4") (pin "d33") (pinfunction "d33_d33") (pintype "bidirectional"))
    )
    (net (code "235") (name "/TRST_L") (class "Default")
      (node (ref "J4") (pin "d34") (pinfunction "d34_d34") (pintype "bidirectional"))
    )
    (net (code "242") (name "3P3V") (class "Default")
      (node (ref "J4") (pin "c39") (pinfunction "c39_c39") (pintype "bidirectional"))
      (node (ref "J4") (pin "d36") (pinfunction "d36_d36") (pintype "bidirectional"))
      (node (ref "J4") (pin "d38") (pinfunction "d38_d38") (pintype "bidirectional"))
      (node (ref "J4") (pin "d40") (pinfunction "d40_d40") (pintype "bidirectional"))
    )
    (net (code "243") (name "GND") (class "Default")
      (node (ref "J4") (pin "a1") (pinfunction "a1_a1") (pintype "bidirectional"))
      (node (ref "J4") (pin "a12") (pinfunction "a12_a12") (pintype "bidirectional"))
      (node (ref "J4") (pin "a13") (pinfunction "a13_a13") (pintype "bidirectional"))
      (node (ref "J4") (pin "a16") (pinfunction "a16_a16") (pintype "bidirectional"))
      (node (ref "J4") (pin "a17") (pinfunction "a17_a17") (pintype "bidirectional"))
      (node (ref "J4") (pin "a20") (pinfunction "a20_a20") (pintype "bidirectional"))
      (node (ref "J4") (pin "a21") (pinfunction "a21_a21") (pintype "bidirectional"))
      (node (ref "J4") (pin "a24") (pinfunction "a24_a24") (pintype "bidirectional"))
      (node (ref "J4") (pin "a25") (pinfunction "a25_a25") (pintype "bidirectional"))
      (node (ref "J4") (pin "a28") (pinfunction "a28_a28") (pintype "bidirectional"))
      (node (ref "J4") (pin "a29") (pinfunction "a29_a29") (pintype "bidirectional"))
      (node (ref "J4") (pin "a32") (pinfunction "a32_a32") (pintype "bidirectional"))
      (node (ref "J4") (pin "a33") (pinfunction "a33_a33") (pintype "bidirectional"))
      (node (ref "J4") (pin "a36") (pinfunction "a36_a36") (pintype "bidirectional"))
      (node (ref "J4") (pin "a37") (pinfunction "a37_a37") (pintype "bidirectional"))
      (node (ref "J4") (pin "a4") (pinfunction "a4_a4") (pintype "bidirectional"))
      (node (ref "J4") (pin "a40") (pinfunction "a40_a40") (pintype "bidirectional"))
      (node (ref "J4") (pin "a5") (pinfunction "a5_a5") (pintype "bidirectional"))
      (node (ref "J4") (pin "a8") (pinfunction "a8_a8") (pintype "bidirectional"))
      (node (ref "J4") (pin "a9") (pinfunction "a9_a9") (pintype "bidirectional"))
      (node (ref "J4") (pin "b10") (pinfunction "b10_b10") (pintype "bidirectional"))
      (node (ref "J4") (pin "b11") (pinfunction "b11_b11") (pintype "bidirectional"))
      (node (ref "J4") (pin "b14") (pinfunction "b14_b14") (pintype "bidirectional"))
      (node (ref "J4") (pin "b15") (pinfunction "b15_b15") (pintype "bidirectional"))
      (node (ref "J4") (pin "b18") (pinfunction "b18_b18") (pintype "bidirectional"))
      (node (ref "J4") (pin "b19") (pinfunction "b19_b19") (pintype "bidirectional"))
      (node (ref "J4") (pin "b2") (pinfunction "b2_b2") (pintype "bidirectional"))
      (node (ref "J4") (pin "b22") (pinfunction "b22_b22") (pintype "bidirectional"))
      (node (ref "J4") (pin "b23") (pinfunction "b23_b23") (pintype "bidirectional"))
      (node (ref "J4") (pin "b26") (pinfunction "b26_b26") (pintype "bidirectional"))
      (node (ref "J4") (pin "b27") (pinfunction "b27_b27") (pintype "bidirectional"))
      (node (ref "J4") (pin "b3") (pinfunction "b3_b3") (pintype "bidirectional"))
      (node (ref "J4") (pin "b30") (pinfunction "b30_b30") (pintype "bidirectional"))
      (node (ref "J4") (pin "b31") (pinfunction "b31_b31") (pintype "bidirectional"))
      (node (ref "J4") (pin "b34") (pinfunction "b34_b34") (pintype "bidirectional"))
      (node (ref "J4") (pin "b35") (pinfunction "b35_b35") (pintype "bidirectional"))
      (node (ref "J4") (pin "b38") (pinfunction "b38_b38") (pintype "bidirectional"))
      (node (ref "J4") (pin "b39") (pinfunction "b39_b39") (pintype "bidirectional"))
      (node (ref "J4") (pin "b6") (pinfunction "b6_b6") (pintype "bidirectional"))
      (node (ref "J4") (pin "b7") (pinfunction "b7_b7") (pintype "bidirectional"))
      (node (ref "J4") (pin "c1") (pinfunction "c1_c1") (pintype "bidirectional"))
      (node (ref "J4") (pin "c12") (pinfunction "c12_c12") (pintype "bidirectional"))
      (node (ref "J4") (pin "c13") (pinfunction "c13_c13") (pintype "bidirectional"))
      (node (ref "J4") (pin "c16") (pinfunction "c16_c16") (pintype "bidirectional"))
      (node (ref "J4") (pin "c17") (pinfunction "c17_c17") (pintype "bidirectional"))
      (node (ref "J4") (pin "c20") (pinfunction "c20_c20") (pintype "bidirectional"))
      (node (ref "J4") (pin "c21") (pinfunction "c21_c21") (pintype "bidirectional"))
      (node (ref "J4") (pin "c24") (pinfunction "c24_c24") (pintype "bidirectional"))
      (node (ref "J4") (pin "c25") (pinfunction "c25_c25") (pintype "bidirectional"))
      (node (ref "J4") (pin "c28") (pinfunction "c28_c28") (pintype "bidirectional"))
      (node (ref "J4") (pin "c29") (pinfunction "c29_c29") (pintype "bidirectional"))
      (node (ref "J4") (pin "c32") (pinfunction "c32_c32") (pintype "bidirectional"))
      (node (ref "J4") (pin "c33") (pinfunction "c33_c33") (pintype "bidirectional"))
      (node (ref "J4") (pin "c36") (pinfunction "c36_c36") (pintype "bidirectional"))
      (node (ref "J4") (pin "c38") (pinfunction "c38_c38") (pintype "bidirectional"))
      (node (ref "J4") (pin "c4") (pinfunction "c4_c4") (pintype "bidirectional"))
      (node (ref "J4") (pin "c40") (pinfunction "c40_c40") (pintype "bidirectional"))
      (node (ref "J4") (pin "c5") (pinfunction "c5_c5") (pintype "bidirectional"))
      (node (ref "J4") (pin "c8") (pinfunction "c8_c8") (pintype "bidirectional"))
      (node (ref "J4") (pin "c9") (pinfunction "c9_c9") (pintype "bidirectional"))
      (node (ref "J4") (pin "d10") (pinfunction "d10_d10") (pintype "bidirectional"))
      (node (ref "J4") (pin "d13") (pinfunction "d13_d13") (pintype "bidirectional"))
      (node (ref "J4") (pin "d16") (pinfunction "d16_d16") (pintype "bidirectional"))
      (node (ref "J4") (pin "d19") (pinfunction "d19_d19") (pintype "bidirectional"))
      (node (ref "J4") (pin "d2") (pinfunction "d2_d2") (pintype "bidirectional"))
      (node (ref "J4") (pin "d22") (pinfunction "d22_d22") (pintype "bidirectional"))
      (node (ref "J4") (pin "d25") (pinfunction "d25_d25") (pintype "bidirectional"))
      (node (ref "J4") (pin "d28") (pinfunction "d28_d28") (pintype "bidirectional"))
      (node (ref "J4") (pin "d3") (pinfunction "d3_d3") (pintype "bidirectional"))
      (node (ref "J4") (pin "d37") (pinfunction "d37_d37") (pintype "bidirectional"))
      (node (ref "J4") (pin "d39") (pinfunction "d39_d39") (pintype "bidirectional"))
      (node (ref "J4") (pin "d6") (pinfunction "d6_d6") (pintype "bidirectional"))
      (node (ref "J4") (pin "d7") (pinfunction "d7_d7") (pintype "bidirectional"))
      (node (ref "J4") (pin "e1") (pinfunction "e1_e1") (pintype "bidirectional"))
      (node (ref "J4") (pin "e11") (pinfunction "e11_e11") (pintype "bidirectional"))
      (node (ref "J4") (pin "e14") (pinfunction "e14_e14") (pintype "bidirectional"))
      (node (ref "J4") (pin "e17") (pinfunction "e17_e17") (pintype "bidirectional"))
      (node (ref "J4") (pin "e20") (pinfunction "e20_e20") (pintype "bidirectional"))
      (node (ref "J4") (pin "e23") (pinfunction "e23_e23") (pintype "bidirectional"))
      (node (ref "J4") (pin "e26") (pinfunction "e26_e26") (pintype "bidirectional"))
      (node (ref "J4") (pin "e29") (pinfunction "e29_e29") (pintype "bidirectional"))
      (node (ref "J4") (pin "e32") (pinfunction "e32_e32") (pintype "bidirectional"))
      (node (ref "J4") (pin "e35") (pinfunction "e35_e35") (pintype "bidirectional"))
      (node (ref "J4") (pin "e38") (pinfunction "e38_e38") (pintype "bidirectional"))
      (node (ref "J4") (pin "e4") (pinfunction "e4_e4") (pintype "bidirectional"))
      (node (ref "J4") (pin "e40") (pinfunction "e40_e40") (pintype "bidirectional"))
      (node (ref "J4") (pin "e5") (pinfunction "e5_e5") (pintype "bidirectional"))
      (node (ref "J4") (pin "e8") (pinfunction "e8_e8") (pintype "bidirectional"))
      (node (ref "J4") (pin "f12") (pinfunction "f12_f12") (pintype "bidirectional"))
      (node (ref "J4") (pin "f15") (pinfunction "f15_f15") (pintype "bidirectional"))
      (node (ref "J4") (pin "f18") (pinfunction "f18_f18") (pintype "bidirectional"))
      (node (ref "J4") (pin "f2") (pinfunction "f2_f2") (pintype "bidirectional"))
      (node (ref "J4") (pin "f21") (pinfunction "f21_f21") (pintype "bidirectional"))
      (node (ref "J4") (pin "f24") (pinfunction "f24_f24") (pintype "bidirectional"))
      (node (ref "J4") (pin "f27") (pinfunction "f27_f27") (pintype "bidirectional"))
      (node (ref "J4") (pin "f3") (pinfunction "f3_f3") (pintype "bidirectional"))
      (node (ref "J4") (pin "f30") (pinfunction "f30_f30") (pintype "bidirectional"))
      (node (ref "J4") (pin "f33") (pinfunction "f33_f33") (pintype "bidirectional"))
      (node (ref "J4") (pin "f36") (pinfunction "f36_f36") (pintype "bidirectional"))
      (node (ref "J4") (pin "f39") (pinfunction "f39_f39") (pintype "bidirectional"))
      (node (ref "J4") (pin "f6") (pinfunction "f6_f6") (pintype "bidirectional"))
      (node (ref "J4") (pin "f9") (pinfunction "f9_f9") (pintype "bidirectional"))
      (node (ref "J4") (pin "g1") (pinfunction "g1_g1") (pintype "bidirectional"))
      (node (ref "J4") (pin "g11") (pinfunction "g11_g11") (pintype "bidirectional"))
      (node (ref "J4") (pin "g14") (pinfunction "g14_g14") (pintype "bidirectional"))
      (node (ref "J4") (pin "g17") (pinfunction "g17_g17") (pintype "bidirectional"))
      (node (ref "J4") (pin "g20") (pinfunction "g20_g20") (pintype "bidirectional"))
      (node (ref "J4") (pin "g23") (pinfunction "g23_g23") (pintype "bidirectional"))
      (node (ref "J4") (pin "g26") (pinfunction "g26_g26") (pintype "bidirectional"))
      (node (ref "J4") (pin "g29") (pinfunction "g29_g29") (pintype "bidirectional"))
      (node (ref "J4") (pin "g32") (pinfunction "g32_g32") (pintype "bidirectional"))
      (node (ref "J4") (pin "g35") (pinfunction "g35_g35") (pintype "bidirectional"))
      (node (ref "J4") (pin "g38") (pinfunction "g38_g38") (pintype "bidirectional"))
      (node (ref "J4") (pin "g4") (pinfunction "g4_g4") (pintype "bidirectional"))
      (node (ref "J4") (pin "g40") (pinfunction "g40_g40") (pintype "bidirectional"))
      (node (ref "J4") (pin "g5") (pinfunction "g5_g5") (pintype "bidirectional"))
      (node (ref "J4") (pin "g8") (pinfunction "g8_g8") (pintype "bidirectional"))
      (node (ref "J4") (pin "h12") (pinfunction "h12_h12") (pintype "bidirectional"))
      (node (ref "J4") (pin "h15") (pinfunction "h15_h15") (pintype "bidirectional"))
      (node (ref "J4") (pin "h18") (pinfunction "h18_h18") (pintype "bidirectional"))
      (node (ref "J4") (pin "h21") (pinfunction "h21_h21") (pintype "bidirectional"))
      (node (ref "J4") (pin "h24") (pinfunction "h24_h24") (pintype "bidirectional"))
      (node (ref "J4") (pin "h27") (pinfunction "h27_h27") (pintype "bidirectional"))
      (node (ref "J4") (pin "h3") (pinfunction "h3_h3") (pintype "bidirectional"))
      (node (ref "J4") (pin "h30") (pinfunction "h30_h30") (pintype "bidirectional"))
      (node (ref "J4") (pin "h33") (pinfunction "h33_h33") (pintype "bidirectional"))
      (node (ref "J4") (pin "h36") (pinfunction "h36_h36") (pintype "bidirectional"))
      (node (ref "J4") (pin "h39") (pinfunction "h39_h39") (pintype "bidirectional"))
      (node (ref "J4") (pin "h6") (pinfunction "h6_h6") (pintype "bidirectional"))
      (node (ref "J4") (pin "h9") (pinfunction "h9_h9") (pintype "bidirectional"))
      (node (ref "J4") (pin "j1") (pinfunction "j1_j1") (pintype "bidirectional"))
      (node (ref "J4") (pin "j11") (pinfunction "j11_j11") (pintype "bidirectional"))
      (node (ref "J4") (pin "j14") (pinfunction "j14_j14") (pintype "bidirectional"))
      (node (ref "J4") (pin "j17") (pinfunction "j17_j17") (pintype "bidirectional"))
      (node (ref "J4") (pin "j20") (pinfunction "j20_j20") (pintype "bidirectional"))
      (node (ref "J4") (pin "j23") (pinfunction "j23_j23") (pintype "bidirectional"))
      (node (ref "J4") (pin "j26") (pinfunction "j26_j26") (pintype "bidirectional"))
      (node (ref "J4") (pin "j29") (pinfunction "j29_j29") (pintype "bidirectional"))
      (node (ref "J4") (pin "j32") (pinfunction "j32_j32") (pintype "bidirectional"))
      (node (ref "J4") (pin "j35") (pinfunction "j35_j35") (pintype "bidirectional"))
      (node (ref "J4") (pin "j38") (pinfunction "j38_j38") (pintype "bidirectional"))
      (node (ref "J4") (pin "j4") (pinfunction "j4_j4") (pintype "bidirectional"))
      (node (ref "J4") (pin "j40") (pinfunction "j40_j40") (pintype "bidirectional"))
      (node (ref "J4") (pin "j5") (pinfunction "j5_j5") (pintype "bidirectional"))
      (node (ref "J4") (pin "j8") (pinfunction "j8_j8") (pintype "bidirectional"))
      (node (ref "J4") (pin "k12") (pinfunction "k12_k12") (pintype "bidirectional"))
      (node (ref "J4") (pin "k15") (pinfunction "k15_k15") (pintype "bidirectional"))
      (node (ref "J4") (pin "k18") (pinfunction "k18_k18") (pintype "bidirectional"))
      (node (ref "J4") (pin "k2") (pinfunction "k2_k2") (pintype "bidirectional"))
      (node (ref "J4") (pin "k21") (pinfunction "k21_k21") (pintype "bidirectional"))
      (node (ref "J4") (pin "k24") (pinfunction "k24_k24") (pintype "bidirectional"))
      (node (ref "J4") (pin "k27") (pinfunction "k27_k27") (pintype "bidirectional"))
      (node (ref "J4") (pin "k3") (pinfunction "k3_k3") (pintype "bidirectional"))
      (node (ref "J4") (pin "k30") (pinfunction "k30_k30") (pintype "bidirectional"))
      (node (ref "J4") (pin "k33") (pinfunction "k33_k33") (pintype "bidirectional"))
      (node (ref "J4") (pin "k36") (pinfunction "k36_k36") (pintype "bidirectional"))
      (node (ref "J4") (pin "k39") (pinfunction "k39_k39") (pintype "bidirectional"))
      (node (ref "J4") (pin "k6") (pinfunction "k6_k6") (pintype "bidirectional"))
      (node (ref "J4") (pin "k9") (pinfunction "k9_k9") (pintype "bidirectional"))
      (node (ref "R83") (pin "2") (pinfunction "2_2") (pintype "passive"))
    )
    (net (code "244") (name "P3V3AUX") (class "Default")
      (node (ref "J4") (pin "d32") (pinfunction "d32_d32") (pintype "bidirectional"))
    )
    (net (code "245") (name "P12V0") (class "Default")
      (node (ref "J4") (pin "c35") (pinfunction "c35_c35") (pintype "bidirectional"))
      (node (ref "J4") (pin "c37") (pinfunction "c37_c37") (pintype "bidirectional"))
    )
    (net (code "246") (name "VADJ") (class "Default")
      (node (ref "J4") (pin "e39") (pinfunction "e39_e39") (pintype "bidirectional"))
      (node (ref "J4") (pin "f40") (pinfunction "f40_f40") (pintype "bidirectional"))
      (node (ref "J4") (pin "g39") (pinfunction "g39_g39") (pintype "bidirectional"))
      (node (ref "J4") (pin "h40") (pinfunction "h40_h40") (pintype "bidirectional"))
    )
    (net (code "247") (name "VIO_B_M2C") (class "Default")
      (node (ref "J4") (pin "j39") (pinfunction "j39_j39") (pintype "bidirectional"))
      (node (ref "J4") (pin "k40") (pinfunction "k40_k40") (pintype "bidirectional"))
    )
    (net (code "248") (name "VREF_B_M2C") (class "Default")
      (node (ref "J4") (pin "h1") (pinfunction "h1_h1") (pintype "bidirectional"))
      (node (ref "J4") (pin "k1") (pinfunction "k1_k1") (pintype "bidirectional"))
    )
  )
)
